# Adafruit_Ultimate_GPS.net
KiCad netlist of a schematic drawn in EAGLE
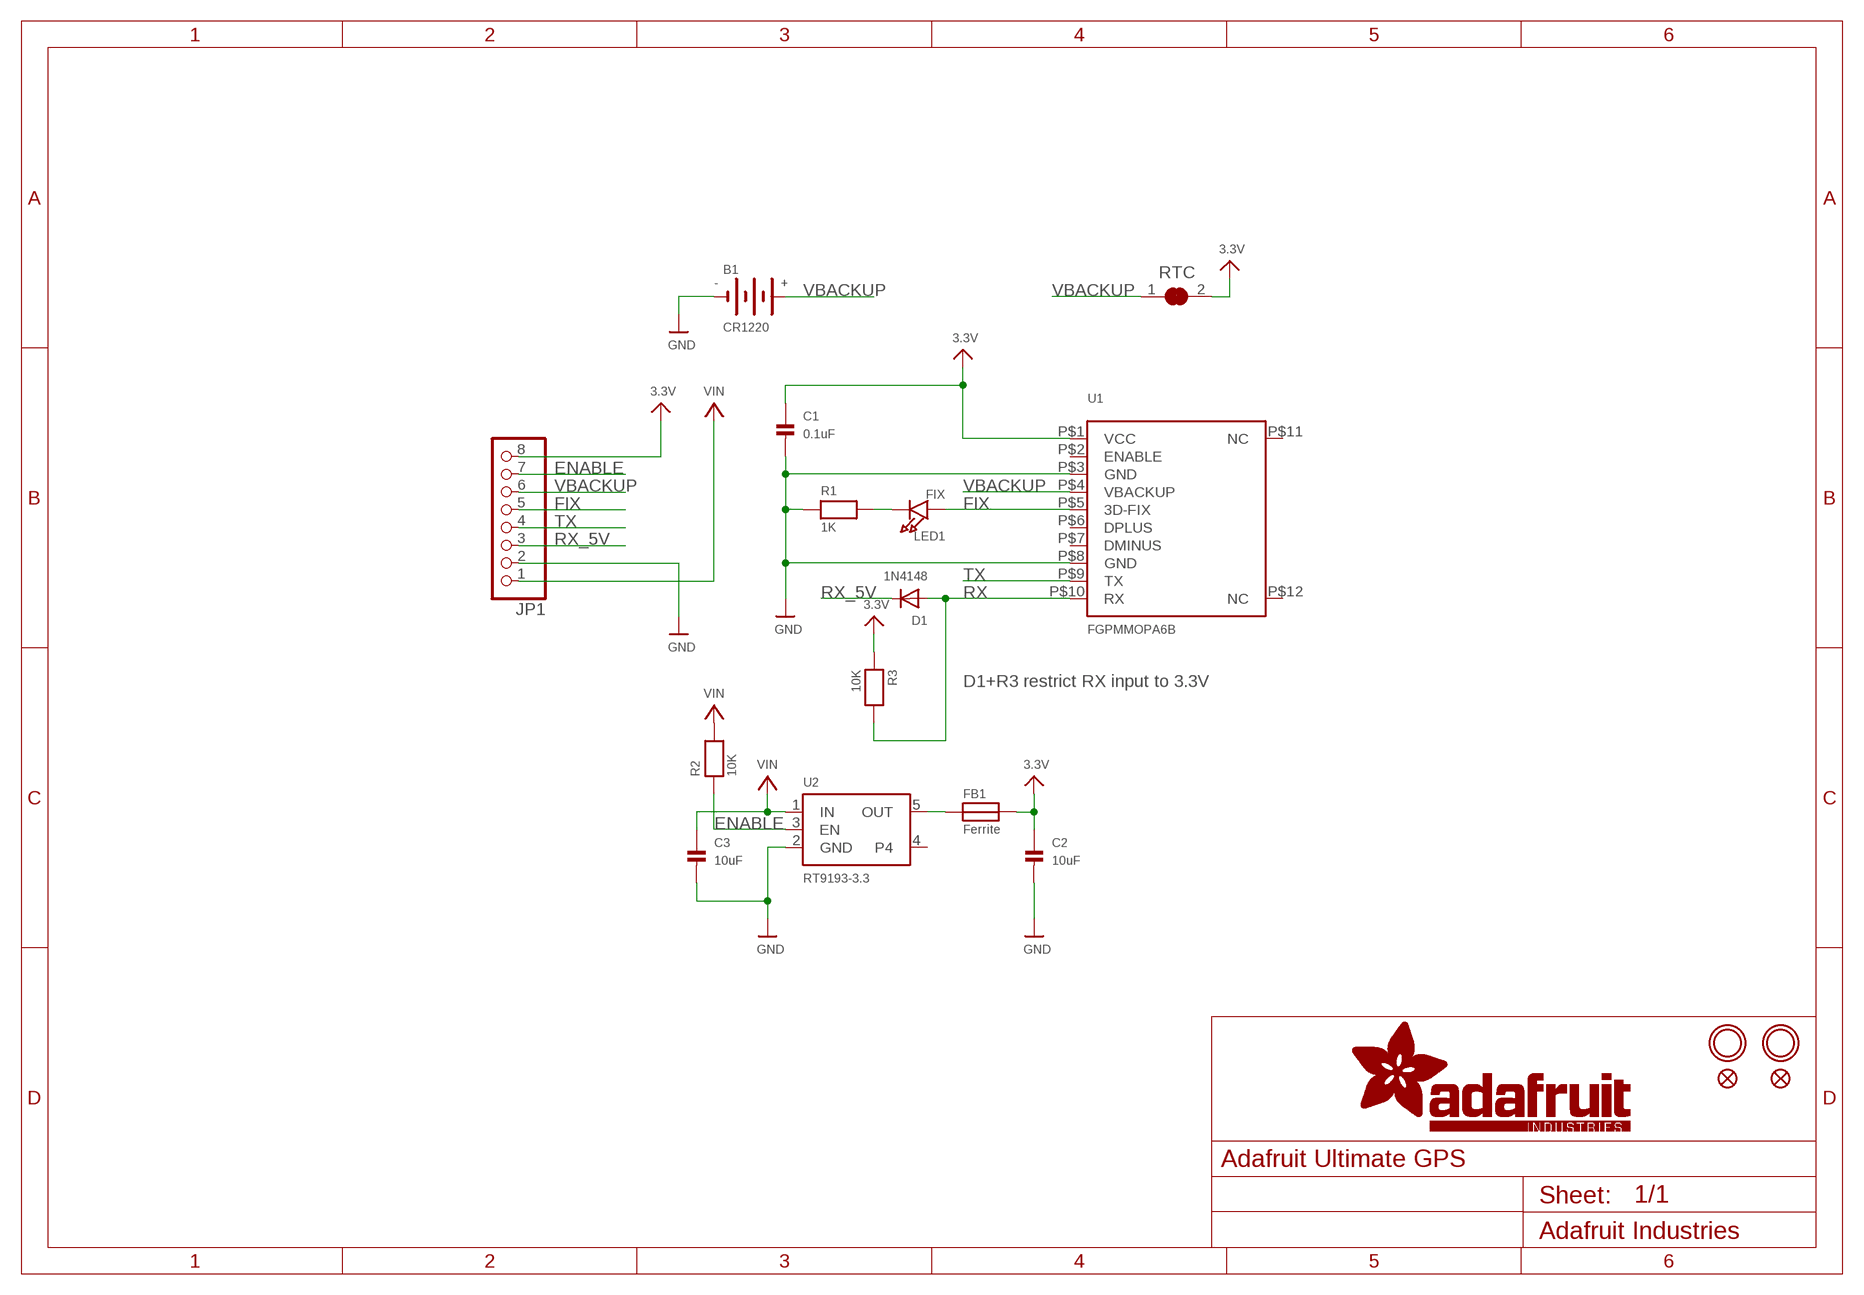
[diagram p0: schematic, sheet 1]

(export (version "E")
  (design (tool "Eeschema 10.0.6"))
  (components
    (comp (ref "B1")
      (value "CR1220")
      (footprint "eagle-import:CR1220")
      (libsource (lib "eagle-import") (part "BATTERYCR1220_SMT"))
    )
    (comp (ref "C1")
      (value "0.1uF")
      (footprint "eagle-import:0805")
      (libsource (lib "eagle-import") (part "CAP_CERAMIC0805"))
    )
    (comp (ref "C2")
      (value "10uF")
      (footprint "eagle-import:0805")
      (libsource (lib "eagle-import") (part "CAP_CERAMIC0805"))
    )
    (comp (ref "C3")
      (value "10uF")
      (footprint "eagle-import:0805")
      (libsource (lib "eagle-import") (part "CAP_CERAMIC0805"))
    )
    (comp (ref "D1")
      (value "1N4148")
      (footprint "eagle-import:SOD-323F")
      (libsource (lib "eagle-import") (part "DIODESOD-323F"))
    )
    (comp (ref "FB1")
      (value "Ferrite")
      (footprint "eagle-import:0805")
      (libsource (lib "eagle-import") (part "FERRITE0805"))
    )
    (comp (ref "FID1")
      (value "FIDUCIAL\"\"")
      (footprint "eagle-import:FIDUCIAL_1MM")
      (libsource (lib "eagle-import") (part "FIDUCIAL{dblquote}{dblquote}"))
    )
    (comp (ref "FID2")
      (value "FIDUCIAL\"\"")
      (footprint "eagle-import:FIDUCIAL_1MM")
      (libsource (lib "eagle-import") (part "FIDUCIAL{dblquote}{dblquote}"))
    )
    (comp (ref "JP1")
      (value "HEADER-1X870MIL")
      (footprint "eagle-import:1X08_ROUND_70")
      (libsource (lib "eagle-import") (part "HEADER-1X870MIL"))
    )
    (comp (ref "LED1")
      (value "FIX")
      (footprint "eagle-import:CHIPLED_0805")
      (libsource (lib "eagle-import") (part "LED0805"))
    )
    (comp (ref "R1")
      (value "1K")
      (footprint "eagle-import:0805")
      (libsource (lib "eagle-import") (part "RESISTOR0805"))
    )
    (comp (ref "R2")
      (value "10K")
      (footprint "eagle-import:0805")
      (libsource (lib "eagle-import") (part "RESISTOR0805"))
    )
    (comp (ref "R3")
      (value "10K")
      (footprint "eagle-import:0805")
      (libsource (lib "eagle-import") (part "RESISTOR0805"))
    )
    (comp (ref "RTC")
      (value "SOLDERJUMPER_CLOSED")
      (footprint "eagle-import:SOLDERJUMPER_CLOSEDWIRE")
      (libsource (lib "eagle-import") (part "SOLDERJUMPER_CLOSED"))
    )
    (comp (ref "U$8")
      (value "MOUNTINGHOLE2.0")
      (footprint "eagle-import:MOUNTINGHOLE_2.0_PLATED")
      (libsource (lib "eagle-import") (part "MOUNTINGHOLE2.0"))
    )
    (comp (ref "U$9")
      (value "MOUNTINGHOLE2.0")
      (footprint "eagle-import:MOUNTINGHOLE_2.0_PLATED")
      (libsource (lib "eagle-import") (part "MOUNTINGHOLE2.0"))
    )
    (comp (ref "U1")
      (value "FGPMMOPA6B")
      (footprint "eagle-import:FGPMMOPA6B")
      (libsource (lib "eagle-import") (part "GPS_FGPMMOPA6B"))
    )
    (comp (ref "U2")
      (value "RT9193-3.3")
      (footprint "eagle-import:SOT23-5")
      (libsource (lib "eagle-import") (part "VREG_SOT23-5"))
    )
  )
  (nets
    (net (code "1") (name "/ENABLE") (class "Default")
      (node (ref "JP1") (pin "7") (pinfunction "7_7") (pintype "passive"))
      (node (ref "R2") (pin "1") (pinfunction "1_1") (pintype "passive"))
      (node (ref "U2") (pin "3") (pinfunction "EN_3") (pintype "bidirectional"))
    )
    (net (code "2") (name "/FIX") (class "Default")
      (node (ref "JP1") (pin "5") (pinfunction "5_5") (pintype "passive"))
      (node (ref "LED1") (pin "A") (pinfunction "A_A") (pintype "passive"))
      (node (ref "U1") (pin "P$5") (pinfunction "3D-FIX_P$5") (pintype "bidirectional"))
    )
    (net (code "3") (name "/RX") (class "Default")
      (node (ref "D1") (pin "A") (pinfunction "A_A") (pintype "passive"))
      (node (ref "R3") (pin "2") (pinfunction "2_2") (pintype "passive"))
      (node (ref "U1") (pin "P$10") (pinfunction "RX_P$10") (pintype "bidirectional"))
    )
    (net (code "4") (name "/RX_5V") (class "Default")
      (node (ref "D1") (pin "C") (pinfunction "C_C") (pintype "passive"))
      (node (ref "JP1") (pin "3") (pinfunction "3_3") (pintype "passive"))
    )
    (net (code "5") (name "/TX") (class "Default")
      (node (ref "JP1") (pin "4") (pinfunction "4_4") (pintype "passive"))
      (node (ref "U1") (pin "P$9") (pinfunction "TX_P$9") (pintype "bidirectional"))
    )
    (net (code "6") (name "/VBACKUP") (class "Default")
      (node (ref "B1") (pin "+$1") (pinfunction "+_+$1") (pintype "passive"))
      (node (ref "JP1") (pin "6") (pinfunction "6_6") (pintype "passive"))
      (node (ref "RTC") (pin "1") (pinfunction "1_1") (pintype "passive"))
      (node (ref "U1") (pin "P$4") (pinfunction "VBACKUP_P$4") (pintype "bidirectional"))
    )
    (net (code "7") (name "3.3V") (class "Default")
      (node (ref "C1") (pin "1") (pinfunction "P$1_1") (pintype "passive"))
      (node (ref "C2") (pin "1") (pinfunction "P$1_1") (pintype "passive"))
      (node (ref "FB1") (pin "2") (pinfunction "P$2_2") (pintype "bidirectional"))
      (node (ref "JP1") (pin "8") (pinfunction "8_8") (pintype "passive"))
      (node (ref "R3") (pin "1") (pinfunction "1_1") (pintype "passive"))
      (node (ref "RTC") (pin "2") (pinfunction "2_2") (pintype "passive"))
      (node (ref "U1") (pin "P$1") (pinfunction "VCC_P$1") (pintype "bidirectional"))
    )
    (net (code "8") (name "GND") (class "Default")
      (node (ref "B1") (pin "-") (pinfunction "-_-") (pintype "passive"))
      (node (ref "C1") (pin "2") (pinfunction "P$2_2") (pintype "passive"))
      (node (ref "C2") (pin "2") (pinfunction "P$2_2") (pintype "passive"))
      (node (ref "C3") (pin "2") (pinfunction "P$2_2") (pintype "passive"))
      (node (ref "JP1") (pin "2") (pinfunction "2_2") (pintype "passive"))
      (node (ref "R1") (pin "1") (pinfunction "1_1") (pintype "passive"))
      (node (ref "U1") (pin "P$3") (pinfunction "GND_P$3") (pintype "bidirectional"))
      (node (ref "U1") (pin "P$8") (pinfunction "GND_P$8") (pintype "bidirectional"))
      (node (ref "U2") (pin "2") (pinfunction "GND_2") (pintype "bidirectional"))
    )
    (net (code "9") (name "Net-(FB1-P$1)") (class "Default")
      (node (ref "FB1") (pin "1") (pinfunction "P$1_1") (pintype "bidirectional"))
      (node (ref "U2") (pin "5") (pinfunction "OUT_5") (pintype "bidirectional"))
    )
    (net (code "10") (name "Net-(LED1-PadC)") (class "Default")
      (node (ref "LED1") (pin "C") (pinfunction "C_C") (pintype "passive"))
      (node (ref "R1") (pin "2") (pinfunction "2_2") (pintype "passive"))
    )
    (net (code "11") (name "VIN") (class "Default")
      (node (ref "C3") (pin "1") (pinfunction "P$1_1") (pintype "passive"))
      (node (ref "JP1") (pin "1") (pinfunction "1_1") (pintype "passive"))
      (node (ref "R2") (pin "2") (pinfunction "2_2") (pintype "passive"))
      (node (ref "U2") (pin "1") (pinfunction "IN_1") (pintype "bidirectional"))
    )
    (net (code "12") (name "unconnected-(U1-DMINUS-PadP$7)") (class "Default")
      (node (ref "U1") (pin "P$7") (pinfunction "DMINUS_P$7") (pintype "bidirectional"))
    )
    (net (code "13") (name "unconnected-(U1-DPLUS-PadP$6)") (class "Default")
      (node (ref "U1") (pin "P$6") (pinfunction "DPLUS_P$6") (pintype "bidirectional"))
    )
    (net (code "14") (name "unconnected-(U1-ENABLE-PadP$2)") (class "Default")
      (node (ref "U1") (pin "P$2") (pinfunction "ENABLE_P$2") (pintype "bidirectional"))
    )
    (net (code "15") (name "unconnected-(U1-NC-PadP$11)") (class "Default")
      (node (ref "U1") (pin "P$11") (pinfunction "NC_P$11") (pintype "bidirectional"))
    )
    (net (code "16") (name "unconnected-(U1-NC-PadP$12)") (class "Default")
      (node (ref "U1") (pin "P$12") (pinfunction "NC_P$12") (pintype "bidirectional"))
    )
    (net (code "17") (name "unconnected-(U2-P4-Pad4)") (class "Default")
      (node (ref "U2") (pin "4") (pinfunction "P4_4") (pintype "bidirectional"))
    )
  )
)
